# Power_Supply_2.net
KiCad netlist of a schematic drawn in Altium Designer
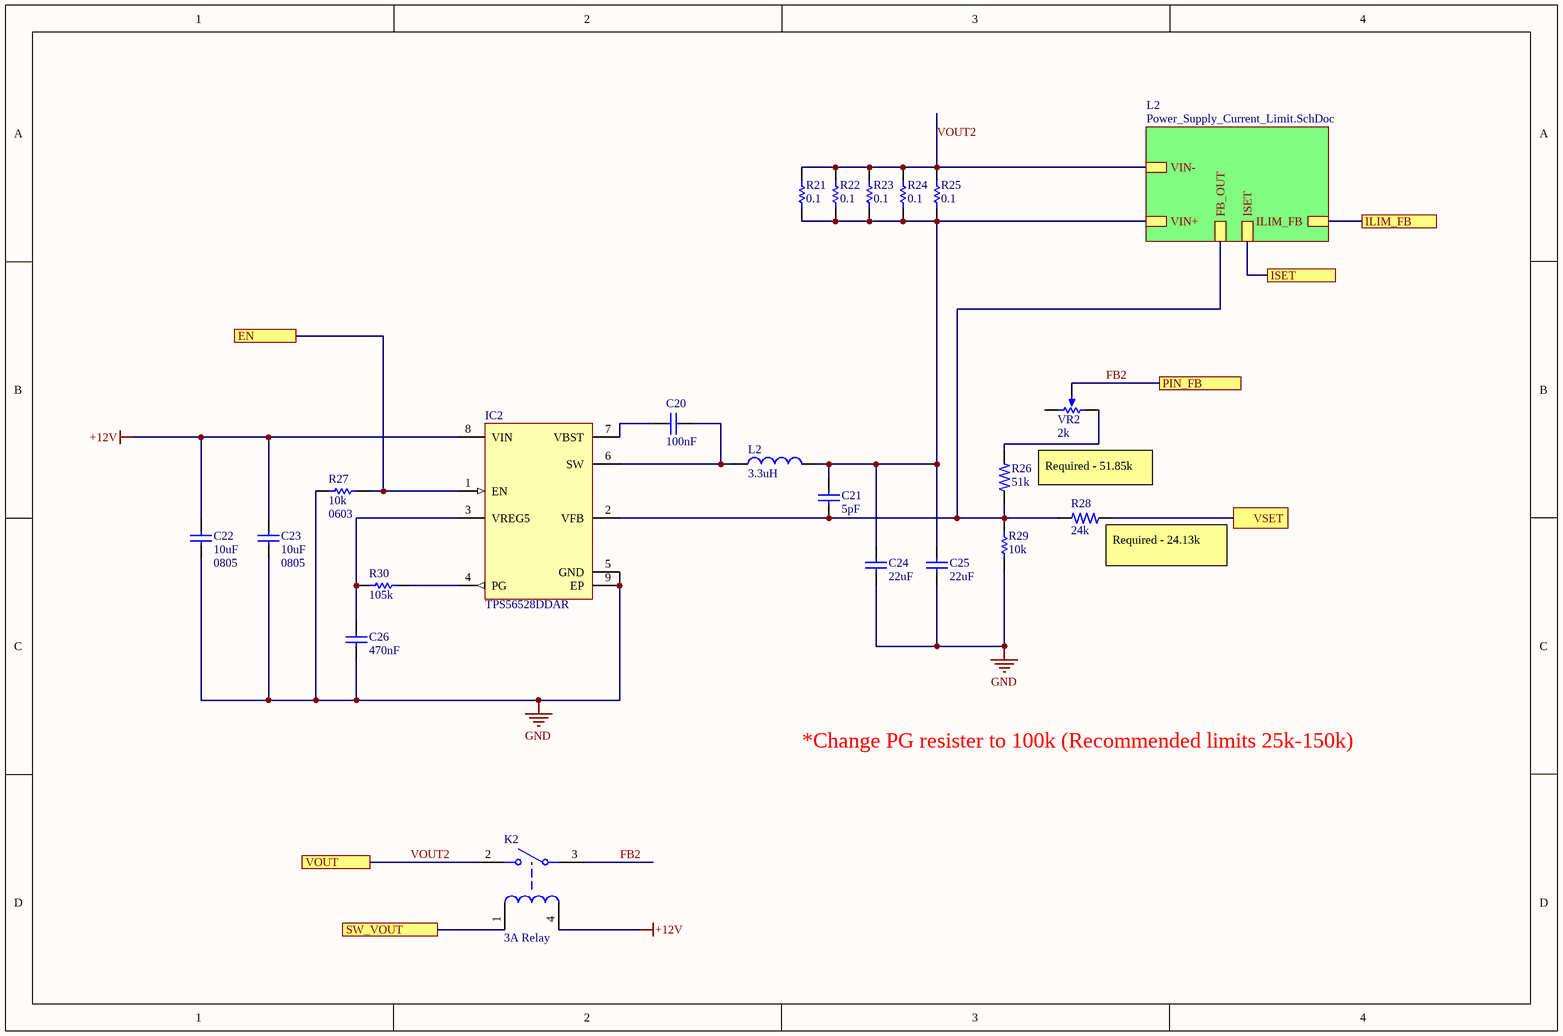
[diagram p0: Power_Supply_2.SchDoc]

(export (version "E")
  (design (tool "Eeschema 10.0.6"))
  (components
    (comp (ref "C20")
      (value "100nF")
      (footprint "CAPC1608X09N")
      (description "0603 10 nF 50 V ± 10% Tolerance X7R Surface Mount Multilayer Ceramic Capacitor")
      (fields
        (field (name "MANUFACTURE PART NUMBER") "CC0603KRX7R9BB104")
        (field (name "MANUFACTURER") "YAGEO")
      )
      (libsource (lib "POWER CARD") (part "CMP-2f55e5122ad9f092-5"))
    )
    (comp (ref "C21")
      (value "5pF")
      (footprint "CAPC1608X09N")
      (description "0603 10 nF 50 V ± 10% Tolerance X7R Surface Mount Multilayer Ceramic Capacitor")
      (fields
        (field (name "MANUFACTURE PART NUMBER") "CL10C050CB8NNNC")
        (field (name "MANUFACTURER") "Samsung Electro-Mechanics")
      )
      (libsource (lib "POWER CARD") (part "CMP-2f55e5122ad9f092-5"))
    )
    (comp (ref "C22")
      (value "10uF")
      (footprint "C0805")
      (description "Cap Ceramic 0.1uF 50V X7R 10% SMD 0805 125C Embossed T/R")
      (fields
        (field (name "MANUFACTURE PART NUMBER") "CL21B106KOQNNNE")
        (field (name "PACKAGE / CASE") "0805")
        (field (name "MANUFACTURER") "Samsung Electro-Mechanics")
      )
      (libsource (lib "POWER CARD") (part "CMP-135114-3"))
    )
    (comp (ref "C23")
      (value "10uF")
      (footprint "C0805")
      (description "Cap Ceramic 0.1uF 50V X7R 10% SMD 0805 125C Embossed T/R")
      (fields
        (field (name "MANUFACTURE PART NUMBER") "CL21B106KOQNNNE")
        (field (name "PACKAGE / CASE") "0805")
        (field (name "MANUFACTURER") "Samsung Electro-Mechanics")
      )
      (libsource (lib "POWER CARD") (part "CMP-135114-3"))
    )
    (comp (ref "C24")
      (value "22uF")
      (footprint "CAPC1608X09N")
      (description "0603 10 nF 50 V ± 10% Tolerance X7R Surface Mount Multilayer Ceramic Capacitor")
      (fields
        (field (name "MANUFACTURE PART NUMBER") "CL10A226MP8NUNE")
        (field (name "MANUFACTURER") "Samsung Electro-Mechanics")
      )
      (libsource (lib "POWER CARD") (part "CMP-2f55e5122ad9f092-5"))
    )
    (comp (ref "C25")
      (value "22uF")
      (footprint "CAPC1608X09N")
      (description "0603 10 nF 50 V ± 10% Tolerance X7R Surface Mount Multilayer Ceramic Capacitor")
      (fields
        (field (name "MANUFACTURE PART NUMBER") "CL10A226MP8NUNE")
        (field (name "MANUFACTURER") "Samsung Electro-Mechanics")
      )
      (libsource (lib "POWER CARD") (part "CMP-2f55e5122ad9f092-5"))
    )
    (comp (ref "C26")
      (value "470nF")
      (footprint "CAPC1608X09N")
      (description "0603 10 nF 50 V ± 10% Tolerance X7R Surface Mount Multilayer Ceramic Capacitor")
      (fields
        (field (name "MANUFACTURE PART NUMBER") "CL10F474ZO8NNNC")
        (field (name "MANUFACTURER") "Samsung Electro-Mechanics")
      )
      (libsource (lib "POWER CARD") (part "CMP-2f55e5122ad9f092-5"))
    )
    (comp (ref "IC2")
      (value "TPS56528DDAR")
      (footprint "PCB-duyb6heo4lj5grkfxin6-1")
      (fields (field (name "MANUFACTURER") "Texas Instruments"))
      (libsource (lib "POWER CARD") (part "CMP-073acf9bf38cd8fd-4"))
    )
    (comp (ref "K2")
      (value "3A Relay")
      (footprint "PCB-ei6nokn2irsc2a7yt94x-1")
      (description "Power Relay 12VDC 3DC/5AAC SPST-NO( (20.5mm 7.2mm 15.3mm)) THT")
      (fields
        (field (name "MANUFACTURER") "Omron Electronics")
        (field (name "MANUFACTURE PART NUMBER") "G5NB-1A-E-DC12")
      )
      (libsource (lib "POWER CARD") (part "CMP-edc624afa9603201-3"))
    )
    (comp (ref "L2")
      (value "3.3uH")
      (footprint "PCB-grsryisdn8451x3s484y-1")
      (description "3.3uH ±20% 10A 11.8m? Power Inductors")
      (fields (field (name "MANUFACTURER") "SXN") (field (name "MANUFACTURE PART NUMBER") "SMMS1040-3R3M"))
      (libsource (lib "POWER CARD") (part "CMP-nvsrvemexzuzshl0ucuq-1"))
    )
    (comp (ref "R21")
      (value "0.1")
      (footprint "RESC3116X07M")
      (description "Res Thick Film 3.2 x 1.6 mm 10K Ohm 1% 0.25W(1/4W) 100ppm/ C Molded SMD Paper T/R")
      (fields
        (field (name "MANUFACTURE PART NUMBER") "1206W4F100LT5E")
        (field (name "MANUFACTURER") "UNI-ROYAL(Uniroyal Elec)")
      )
      (libsource (lib "POWER CARD") (part "CMP-90ca5a8d69034f0d-5"))
    )
    (comp (ref "R22")
      (value "0.1")
      (footprint "RESC3116X07M")
      (description "Res Thick Film 3.2 x 1.6 mm 10K Ohm 1% 0.25W(1/4W) 100ppm/ C Molded SMD Paper T/R")
      (fields
        (field (name "MANUFACTURE PART NUMBER") "1206W4F100LT5E")
        (field (name "MANUFACTURER") "UNI-ROYAL(Uniroyal Elec)")
      )
      (libsource (lib "POWER CARD") (part "CMP-90ca5a8d69034f0d-5"))
    )
    (comp (ref "R23")
      (value "0.1")
      (footprint "RESC3116X07M")
      (description "Res Thick Film 3.2 x 1.6 mm 10K Ohm 1% 0.25W(1/4W) 100ppm/ C Molded SMD Paper T/R")
      (fields
        (field (name "MANUFACTURE PART NUMBER") "1206W4F100LT5E")
        (field (name "MANUFACTURER") "UNI-ROYAL(Uniroyal Elec)")
      )
      (libsource (lib "POWER CARD") (part "CMP-90ca5a8d69034f0d-5"))
    )
    (comp (ref "R24")
      (value "0.1")
      (footprint "RESC3116X07M")
      (description "Res Thick Film 3.2 x 1.6 mm 10K Ohm 1% 0.25W(1/4W) 100ppm/ C Molded SMD Paper T/R")
      (fields
        (field (name "MANUFACTURE PART NUMBER") "1206W4F100LT5E")
        (field (name "MANUFACTURER") "UNI-ROYAL(Uniroyal Elec)")
      )
      (libsource (lib "POWER CARD") (part "CMP-90ca5a8d69034f0d-5"))
    )
    (comp (ref "R25")
      (value "0.1")
      (footprint "RESC3116X07M")
      (description "Res Thick Film 3.2 x 1.6 mm 10K Ohm 1% 0.25W(1/4W) 100ppm/ C Molded SMD Paper T/R")
      (fields
        (field (name "MANUFACTURE PART NUMBER") "1206W4F100LT5E")
        (field (name "MANUFACTURER") "UNI-ROYAL(Uniroyal Elec)")
      )
      (libsource (lib "POWER CARD") (part "CMP-90ca5a8d69034f0d-5"))
    )
    (comp (ref "R26")
      (value "51k")
      (footprint "PCB-3elf45qdqizoabmczrxc-1")
      (description "Surface Mount Thick Film Resistor, RC Series, 1 kohm, 100 mW, - 1%, 50 V, 0603 [1608 Metric]")
      (fields
        (field (name "MANUFACTURER") "Walsin Tech Group")
        (field (name "MANUFACTURE PART NUMBER") "WR06X513 JTL")
      )
      (libsource (lib "POWER CARD") (part "CMP-1853278-23"))
    )
    (comp (ref "R27")
      (value "10k")
      (footprint "gen0603-2")
      (description "Surface Mount Thick Film Resistor, RC Series, 1 kohm, 100 mW, - 1%, 50 V, 0603 [1608 Metric]")
      (fields
        (field (name "MANUFACTURER") "YAGEO")
        (field (name "MANUFACTURE PART NUMBER") "RC0603FR-0710KL")
        (field (name "PACKAGE / CASE") "0603")
      )
      (libsource (lib "POWER CARD") (part "CMP-1853278-27"))
    )
    (comp (ref "R28")
      (value "24k")
      (footprint "PCB-3elf45qdqizoabmczrxc-1")
      (description "Surface Mount Thick Film Resistor, RC Series, 1 kohm, 100 mW, - 1%, 50 V, 0603 [1608 Metric]")
      (fields
        (field (name "MANUFACTURER") "UNI-ROYAL(Uniroyal Elec)")
        (field (name "MANUFACTURE PART NUMBER") "0603WAJ0243T5E")
      )
      (libsource (lib "POWER CARD") (part "CMP-1853278-23"))
    )
    (comp (ref "R29")
      (value "10k")
      (footprint "gen0603-2")
      (description "Surface Mount Thick Film Resistor, RC Series, 1 kohm, 100 mW, - 1%, 50 V, 0603 [1608 Metric]")
      (fields
        (field (name "MANUFACTURER") "YAGEO")
        (field (name "MANUFACTURE PART NUMBER") "RC0603FR-0710KL")
      )
      (libsource (lib "POWER CARD") (part "CMP-1853278-27"))
    )
    (comp (ref "R30")
      (value "105k")
      (footprint "gen0603-2")
      (description "Surface Mount Thick Film Resistor, RC Series, 1 kohm, 100 mW, - 1%, 50 V, 0603 [1608 Metric]")
      (fields
        (field (name "MANUFACTURER") "UNI-ROYAL")
        (field (name "MANUFACTURE PART NUMBER") "0603WAF1053T5E")
      )
      (libsource (lib "POWER CARD") (part "CMP-1853278-27"))
    )
    (comp (ref "VR2")
      (value "2k")
      (footprint "PCB-5abvnr99iwiiosfurk6j-1")
      (description "Res Cermet Trimmer 2K Ohm 10% 1/2W 25(Elec)Turn 2.19mm (9.53 X 4.83 X 11.55mm) Pin Thru-Hole Tube")
      (fields
        (field (name "MANUFACTURE PART NUMBER") "3296W-1-202")
        (field (name "MANUFACTURER") "BOCHEN(Chengdu Guosheng Tech)")
      )
      (libsource (lib "POWER CARD") (part "CMP-a8df61d7bf077718-3"))
    )
  )
  (nets
    (net (code "1") (name "+12V") (class "Default")
      (node (ref "C22") (pin "2") (pinfunction "2_2") (pintype "passive"))
      (node (ref "C23") (pin "2") (pinfunction "2_2") (pintype "passive"))
      (node (ref "IC2") (pin "8") (pinfunction "VIN_8") (pintype "passive"))
      (node (ref "K2") (pin "4") (pinfunction "4_4") (pintype "passive"))
    )
    (net (code "2") (name "/EN") (class "Default")
      (node (ref "IC2") (pin "1") (pinfunction "EN_1") (pintype "input"))
      (node (ref "R27") (pin "1") (pinfunction "1_1") (pintype "passive"))
    )
    (net (code "3") (name "/FB2") (class "Default")
      (node (ref "K2") (pin "3") (pinfunction "3_3") (pintype "passive"))
      (node (ref "VR2") (pin "2") (pinfunction "WIPER_2") (pintype "passive"))
    )
    (net (code "4") (name "/FB_OUT") (class "Default")
      (node (ref "C21") (pin "1") (pinfunction "1_1") (pintype "passive"))
      (node (ref "IC2") (pin "2") (pinfunction "VFB_2") (pintype "passive"))
      (node (ref "R26") (pin "1") (pinfunction "1_1") (pintype "passive"))
      (node (ref "R28") (pin "2") (pinfunction "2_2") (pintype "passive"))
      (node (ref "R29") (pin "2") (pinfunction "2_2") (pintype "passive"))
    )
    (net (code "7") (name "/SW_VOUT") (class "Default")
      (node (ref "K2") (pin "1") (pinfunction "1_1") (pintype "passive"))
    )
    (net (code "8") (name "/VIN+") (class "Default")
      (node (ref "C21") (pin "2") (pinfunction "2_2") (pintype "passive"))
      (node (ref "C24") (pin "2") (pinfunction "2_2") (pintype "passive"))
      (node (ref "C25") (pin "2") (pinfunction "2_2") (pintype "passive"))
      (node (ref "L2") (pin "2") (pinfunction "2_2") (pintype "passive"))
      (node (ref "R21") (pin "2") (pinfunction "2_2") (pintype "passive"))
      (node (ref "R22") (pin "1") (pinfunction "1_1") (pintype "passive"))
      (node (ref "R23") (pin "1") (pinfunction "1_1") (pintype "passive"))
      (node (ref "R24") (pin "1") (pinfunction "1_1") (pintype "passive"))
      (node (ref "R25") (pin "1") (pinfunction "1_1") (pintype "passive"))
    )
    (net (code "9") (name "/VOUT2") (class "Default")
      (node (ref "K2") (pin "2") (pinfunction "2_2") (pintype "passive"))
      (node (ref "R21") (pin "1") (pinfunction "1_1") (pintype "passive"))
      (node (ref "R22") (pin "2") (pinfunction "2_2") (pintype "passive"))
      (node (ref "R23") (pin "2") (pinfunction "2_2") (pintype "passive"))
      (node (ref "R24") (pin "2") (pinfunction "2_2") (pintype "passive"))
      (node (ref "R25") (pin "2") (pinfunction "2_2") (pintype "passive"))
    )
    (net (code "10") (name "/VSET") (class "Default")
      (node (ref "R28") (pin "1") (pinfunction "1_1") (pintype "passive"))
    )
    (net (code "11") (name "GND") (class "Default")
      (node (ref "C22") (pin "1") (pinfunction "1_1") (pintype "passive"))
      (node (ref "C23") (pin "1") (pinfunction "1_1") (pintype "passive"))
      (node (ref "C24") (pin "1") (pinfunction "1_1") (pintype "passive"))
      (node (ref "C25") (pin "1") (pinfunction "1_1") (pintype "passive"))
      (node (ref "C26") (pin "1") (pinfunction "1_1") (pintype "passive"))
      (node (ref "IC2") (pin "5") (pinfunction "GND_5") (pintype "passive"))
      (node (ref "IC2") (pin "9") (pinfunction "EP_9") (pintype "passive"))
      (node (ref "R27") (pin "2") (pinfunction "2_2") (pintype "passive"))
      (node (ref "R29") (pin "1") (pinfunction "1_1") (pintype "passive"))
    )
    (net (code "12") (name "Net-(IC2-PG)") (class "Default")
      (node (ref "IC2") (pin "4") (pinfunction "PG_4") (pintype "output"))
      (node (ref "R30") (pin "1") (pinfunction "1_1") (pintype "passive"))
    )
    (net (code "13") (name "Net-(IC2-SW)") (class "Default")
      (node (ref "C20") (pin "1") (pinfunction "1_1") (pintype "passive"))
      (node (ref "IC2") (pin "6") (pinfunction "SW_6") (pintype "passive"))
      (node (ref "L2") (pin "1") (pinfunction "1_1") (pintype "passive"))
    )
    (net (code "14") (name "Net-(IC2-VBST)") (class "Default")
      (node (ref "C20") (pin "2") (pinfunction "2_2") (pintype "passive"))
      (node (ref "IC2") (pin "7") (pinfunction "VBST_7") (pintype "passive"))
    )
    (net (code "15") (name "Net-(IC2-VREG5)") (class "Default")
      (node (ref "C26") (pin "2") (pinfunction "2_2") (pintype "passive"))
      (node (ref "IC2") (pin "3") (pinfunction "VREG5_3") (pintype "passive"))
      (node (ref "R30") (pin "2") (pinfunction "2_2") (pintype "passive"))
    )
    (net (code "16") (name "Net-(VR2-CW)") (class "Default")
      (node (ref "R26") (pin "2") (pinfunction "2_2") (pintype "passive"))
      (node (ref "VR2") (pin "3") (pinfunction "CW_3") (pintype "passive"))
    )
    (net (code "17") (name "unconnected-(VR2-CCW-Pad1)") (class "Default")
      (node (ref "VR2") (pin "1") (pinfunction "CCW_1") (pintype "passive"))
    )
  )
)
